# sensor_garis_v2.net
KiCad netlist of a schematic drawn in EAGLE
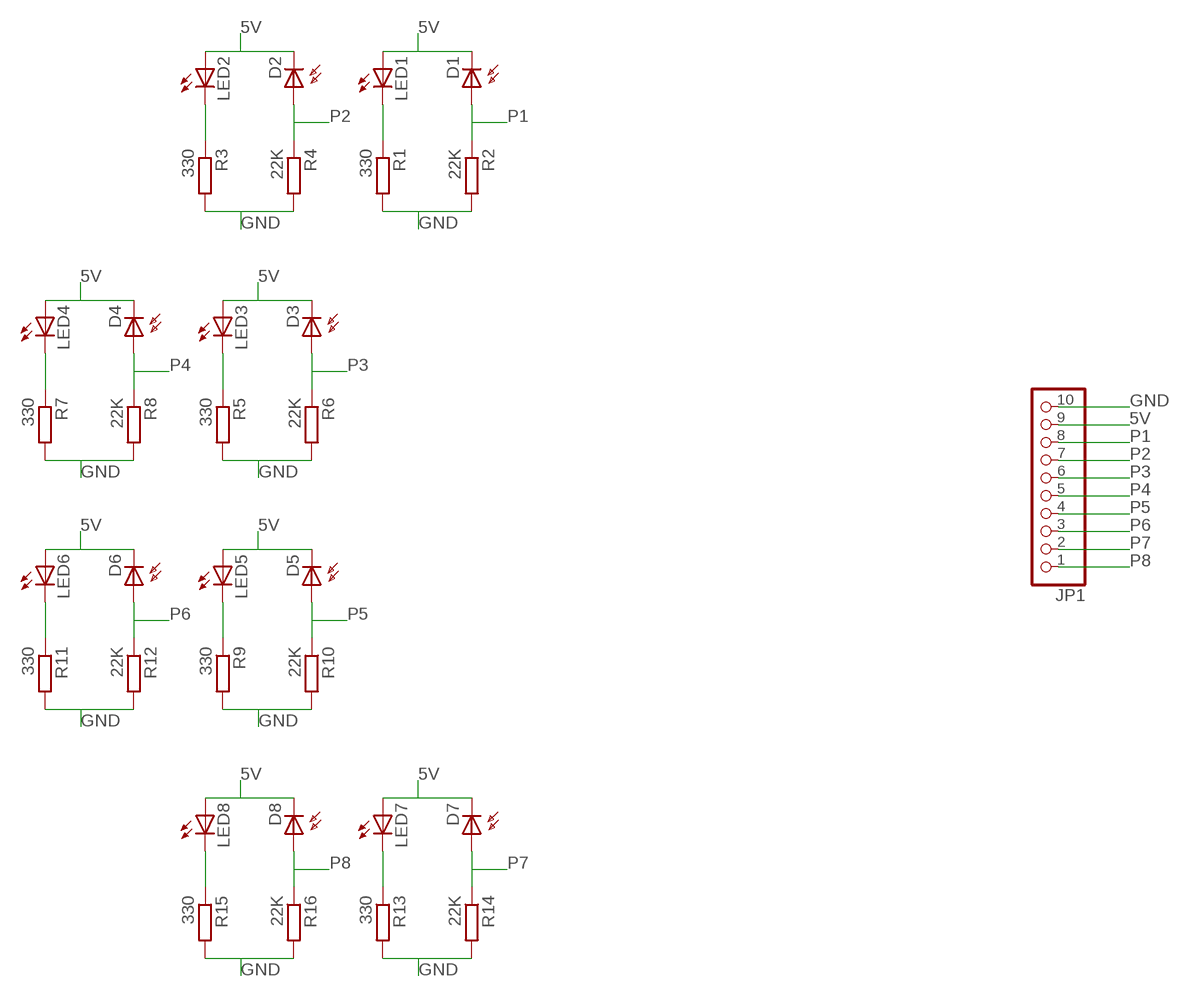
[diagram p0: schematic, sheet 1]

(export (version "E")
  (design (tool "Eeschema 10.0.6"))
  (components
    (comp (ref "D1")
      (value "BPX65")
      (footprint "eagle-import:BPX65")
      (fields (field (name "MPN") "BPX65."))
      (libsource (lib "eagle-import") (part "BPX65"))
    )
    (comp (ref "D2")
      (value "BPX65")
      (footprint "eagle-import:BPX65")
      (fields (field (name "MPN") "BPX65."))
      (libsource (lib "eagle-import") (part "BPX65"))
    )
    (comp (ref "D3")
      (value "BPX65")
      (footprint "eagle-import:BPX65")
      (fields (field (name "MPN") "BPX65."))
      (libsource (lib "eagle-import") (part "BPX65"))
    )
    (comp (ref "D4")
      (value "BPX65")
      (footprint "eagle-import:BPX65")
      (fields (field (name "MPN") "BPX65."))
      (libsource (lib "eagle-import") (part "BPX65"))
    )
    (comp (ref "D5")
      (value "BPX65")
      (footprint "eagle-import:BPX65")
      (fields (field (name "MPN") "BPX65."))
      (libsource (lib "eagle-import") (part "BPX65"))
    )
    (comp (ref "D6")
      (value "BPX65")
      (footprint "eagle-import:BPX65")
      (fields (field (name "MPN") "BPX65."))
      (libsource (lib "eagle-import") (part "BPX65"))
    )
    (comp (ref "D7")
      (value "BPX65")
      (footprint "eagle-import:BPX65")
      (fields (field (name "MPN") "BPX65."))
      (libsource (lib "eagle-import") (part "BPX65"))
    )
    (comp (ref "D8")
      (value "BPX65")
      (footprint "eagle-import:BPX65")
      (fields (field (name "MPN") "BPX65."))
      (libsource (lib "eagle-import") (part "BPX65"))
    )
    (comp (ref "JP1")
      (value "PINHD-1X10")
      (footprint "eagle-import:1X10")
      (libsource (lib "eagle-import") (part "PINHD-1X10"))
    )
    (comp (ref "LED1")
      (value "LED3MM")
      (footprint "eagle-import:LED3MM")
      (libsource (lib "eagle-import") (part "LED3MM"))
    )
    (comp (ref "LED2")
      (value "LED3MM")
      (footprint "eagle-import:LED3MM")
      (libsource (lib "eagle-import") (part "LED3MM"))
    )
    (comp (ref "LED3")
      (value "LED3MM")
      (footprint "eagle-import:LED3MM")
      (libsource (lib "eagle-import") (part "LED3MM"))
    )
    (comp (ref "LED4")
      (value "LED3MM")
      (footprint "eagle-import:LED3MM")
      (libsource (lib "eagle-import") (part "LED3MM"))
    )
    (comp (ref "LED5")
      (value "LED3MM")
      (footprint "eagle-import:LED3MM")
      (libsource (lib "eagle-import") (part "LED3MM"))
    )
    (comp (ref "LED6")
      (value "LED3MM")
      (footprint "eagle-import:LED3MM")
      (libsource (lib "eagle-import") (part "LED3MM"))
    )
    (comp (ref "LED7")
      (value "LED3MM")
      (footprint "eagle-import:LED3MM")
      (libsource (lib "eagle-import") (part "LED3MM"))
    )
    (comp (ref "LED8")
      (value "LED3MM")
      (footprint "eagle-import:LED3MM")
      (libsource (lib "eagle-import") (part "LED3MM"))
    )
    (comp (ref "R1")
      (value "330")
      (footprint "eagle-import:0207_7")
      (libsource (lib "eagle-import") (part "R-EU_0207/7"))
    )
    (comp (ref "R2")
      (value "22K")
      (footprint "eagle-import:0207_7")
      (libsource (lib "eagle-import") (part "R-EU_0207/7"))
    )
    (comp (ref "R3")
      (value "330")
      (footprint "eagle-import:0207_7")
      (libsource (lib "eagle-import") (part "R-EU_0207/7"))
    )
    (comp (ref "R4")
      (value "22K")
      (footprint "eagle-import:0207_7")
      (libsource (lib "eagle-import") (part "R-EU_0207/7"))
    )
    (comp (ref "R5")
      (value "330")
      (footprint "eagle-import:0207_7")
      (libsource (lib "eagle-import") (part "R-EU_0207/7"))
    )
    (comp (ref "R6")
      (value "22K")
      (footprint "eagle-import:0207_7")
      (libsource (lib "eagle-import") (part "R-EU_0207/7"))
    )
    (comp (ref "R7")
      (value "330")
      (footprint "eagle-import:0207_7")
      (libsource (lib "eagle-import") (part "R-EU_0207/7"))
    )
    (comp (ref "R8")
      (value "22K")
      (footprint "eagle-import:0207_7")
      (libsource (lib "eagle-import") (part "R-EU_0207/7"))
    )
    (comp (ref "R9")
      (value "330")
      (footprint "eagle-import:0207_7")
      (libsource (lib "eagle-import") (part "R-EU_0207/7"))
    )
    (comp (ref "R10")
      (value "22K")
      (footprint "eagle-import:0207_7")
      (libsource (lib "eagle-import") (part "R-EU_0207/7"))
    )
    (comp (ref "R11")
      (value "330")
      (footprint "eagle-import:0207_7")
      (libsource (lib "eagle-import") (part "R-EU_0207/7"))
    )
    (comp (ref "R12")
      (value "22K")
      (footprint "eagle-import:0207_7")
      (libsource (lib "eagle-import") (part "R-EU_0207/7"))
    )
    (comp (ref "R13")
      (value "330")
      (footprint "eagle-import:0207_7")
      (libsource (lib "eagle-import") (part "R-EU_0207/7"))
    )
    (comp (ref "R14")
      (value "22K")
      (footprint "eagle-import:0207_7")
      (libsource (lib "eagle-import") (part "R-EU_0207/7"))
    )
    (comp (ref "R15")
      (value "330")
      (footprint "eagle-import:0207_7")
      (libsource (lib "eagle-import") (part "R-EU_0207/7"))
    )
    (comp (ref "R16")
      (value "22K")
      (footprint "eagle-import:0207_7")
      (libsource (lib "eagle-import") (part "R-EU_0207/7"))
    )
  )
  (nets
    (net (code "1") (name "/5V") (class "Default")
      (node (ref "D1") (pin "K") (pinfunction "C_K") (pintype "passive"))
      (node (ref "D2") (pin "K") (pinfunction "C_K") (pintype "passive"))
      (node (ref "D3") (pin "K") (pinfunction "C_K") (pintype "passive"))
      (node (ref "D4") (pin "K") (pinfunction "C_K") (pintype "passive"))
      (node (ref "D5") (pin "K") (pinfunction "C_K") (pintype "passive"))
      (node (ref "D6") (pin "K") (pinfunction "C_K") (pintype "passive"))
      (node (ref "D7") (pin "K") (pinfunction "C_K") (pintype "passive"))
      (node (ref "D8") (pin "K") (pinfunction "C_K") (pintype "passive"))
      (node (ref "JP1") (pin "9") (pinfunction "9_9") (pintype "passive"))
      (node (ref "LED1") (pin "A") (pinfunction "A_A") (pintype "passive"))
      (node (ref "LED2") (pin "A") (pinfunction "A_A") (pintype "passive"))
      (node (ref "LED3") (pin "A") (pinfunction "A_A") (pintype "passive"))
      (node (ref "LED4") (pin "A") (pinfunction "A_A") (pintype "passive"))
      (node (ref "LED5") (pin "A") (pinfunction "A_A") (pintype "passive"))
      (node (ref "LED6") (pin "A") (pinfunction "A_A") (pintype "passive"))
      (node (ref "LED7") (pin "A") (pinfunction "A_A") (pintype "passive"))
      (node (ref "LED8") (pin "A") (pinfunction "A_A") (pintype "passive"))
    )
    (net (code "2") (name "/GND") (class "Default")
      (node (ref "JP1") (pin "10") (pinfunction "10_10") (pintype "passive"))
      (node (ref "R1") (pin "2") (pinfunction "2_2") (pintype "passive"))
      (node (ref "R10") (pin "2") (pinfunction "2_2") (pintype "passive"))
      (node (ref "R11") (pin "2") (pinfunction "2_2") (pintype "passive"))
      (node (ref "R12") (pin "2") (pinfunction "2_2") (pintype "passive"))
      (node (ref "R13") (pin "2") (pinfunction "2_2") (pintype "passive"))
      (node (ref "R14") (pin "2") (pinfunction "2_2") (pintype "passive"))
      (node (ref "R15") (pin "2") (pinfunction "2_2") (pintype "passive"))
      (node (ref "R16") (pin "2") (pinfunction "2_2") (pintype "passive"))
      (node (ref "R2") (pin "2") (pinfunction "2_2") (pintype "passive"))
      (node (ref "R3") (pin "2") (pinfunction "2_2") (pintype "passive"))
      (node (ref "R4") (pin "2") (pinfunction "2_2") (pintype "passive"))
      (node (ref "R5") (pin "2") (pinfunction "2_2") (pintype "passive"))
      (node (ref "R6") (pin "2") (pinfunction "2_2") (pintype "passive"))
      (node (ref "R7") (pin "2") (pinfunction "2_2") (pintype "passive"))
      (node (ref "R8") (pin "2") (pinfunction "2_2") (pintype "passive"))
      (node (ref "R9") (pin "2") (pinfunction "2_2") (pintype "passive"))
    )
    (net (code "3") (name "/P1") (class "Default")
      (node (ref "D1") (pin "A") (pinfunction "A_A") (pintype "passive"))
      (node (ref "JP1") (pin "8") (pinfunction "8_8") (pintype "passive"))
      (node (ref "R2") (pin "1") (pinfunction "1_1") (pintype "passive"))
    )
    (net (code "4") (name "/P2") (class "Default")
      (node (ref "D2") (pin "A") (pinfunction "A_A") (pintype "passive"))
      (node (ref "JP1") (pin "7") (pinfunction "7_7") (pintype "passive"))
      (node (ref "R4") (pin "1") (pinfunction "1_1") (pintype "passive"))
    )
    (net (code "5") (name "/P3") (class "Default")
      (node (ref "D3") (pin "A") (pinfunction "A_A") (pintype "passive"))
      (node (ref "JP1") (pin "6") (pinfunction "6_6") (pintype "passive"))
      (node (ref "R6") (pin "1") (pinfunction "1_1") (pintype "passive"))
    )
    (net (code "6") (name "/P4") (class "Default")
      (node (ref "D4") (pin "A") (pinfunction "A_A") (pintype "passive"))
      (node (ref "JP1") (pin "5") (pinfunction "5_5") (pintype "passive"))
      (node (ref "R8") (pin "1") (pinfunction "1_1") (pintype "passive"))
    )
    (net (code "7") (name "/P5") (class "Default")
      (node (ref "D5") (pin "A") (pinfunction "A_A") (pintype "passive"))
      (node (ref "JP1") (pin "4") (pinfunction "4_4") (pintype "passive"))
      (node (ref "R10") (pin "1") (pinfunction "1_1") (pintype "passive"))
    )
    (net (code "8") (name "/P6") (class "Default")
      (node (ref "D6") (pin "A") (pinfunction "A_A") (pintype "passive"))
      (node (ref "JP1") (pin "3") (pinfunction "3_3") (pintype "passive"))
      (node (ref "R12") (pin "1") (pinfunction "1_1") (pintype "passive"))
    )
    (net (code "9") (name "/P7") (class "Default")
      (node (ref "D7") (pin "A") (pinfunction "A_A") (pintype "passive"))
      (node (ref "JP1") (pin "2") (pinfunction "2_2") (pintype "passive"))
      (node (ref "R14") (pin "1") (pinfunction "1_1") (pintype "passive"))
    )
    (net (code "10") (name "/P8") (class "Default")
      (node (ref "D8") (pin "A") (pinfunction "A_A") (pintype "passive"))
      (node (ref "JP1") (pin "1") (pinfunction "1_1") (pintype "passive"))
      (node (ref "R16") (pin "1") (pinfunction "1_1") (pintype "passive"))
    )
    (net (code "11") (name "Net-(LED1-C)") (class "Default")
      (node (ref "LED1") (pin "K") (pinfunction "C_K") (pintype "passive"))
      (node (ref "R1") (pin "1") (pinfunction "1_1") (pintype "passive"))
    )
    (net (code "12") (name "Net-(LED2-C)") (class "Default")
      (node (ref "LED2") (pin "K") (pinfunction "C_K") (pintype "passive"))
      (node (ref "R3") (pin "1") (pinfunction "1_1") (pintype "passive"))
    )
    (net (code "13") (name "Net-(LED3-C)") (class "Default")
      (node (ref "LED3") (pin "K") (pinfunction "C_K") (pintype "passive"))
      (node (ref "R5") (pin "1") (pinfunction "1_1") (pintype "passive"))
    )
    (net (code "14") (name "Net-(LED4-C)") (class "Default")
      (node (ref "LED4") (pin "K") (pinfunction "C_K") (pintype "passive"))
      (node (ref "R7") (pin "1") (pinfunction "1_1") (pintype "passive"))
    )
    (net (code "15") (name "Net-(LED5-C)") (class "Default")
      (node (ref "LED5") (pin "K") (pinfunction "C_K") (pintype "passive"))
      (node (ref "R9") (pin "1") (pinfunction "1_1") (pintype "passive"))
    )
    (net (code "16") (name "Net-(LED6-C)") (class "Default")
      (node (ref "LED6") (pin "K") (pinfunction "C_K") (pintype "passive"))
      (node (ref "R11") (pin "1") (pinfunction "1_1") (pintype "passive"))
    )
    (net (code "17") (name "Net-(LED7-C)") (class "Default")
      (node (ref "LED7") (pin "K") (pinfunction "C_K") (pintype "passive"))
      (node (ref "R13") (pin "1") (pinfunction "1_1") (pintype "passive"))
    )
    (net (code "18") (name "Net-(LED8-C)") (class "Default")
      (node (ref "LED8") (pin "K") (pinfunction "C_K") (pintype "passive"))
      (node (ref "R15") (pin "1") (pinfunction "1_1") (pintype "passive"))
    )
  )
)
